# JTAG.net
KiCad netlist of a schematic drawn in Altium Designer
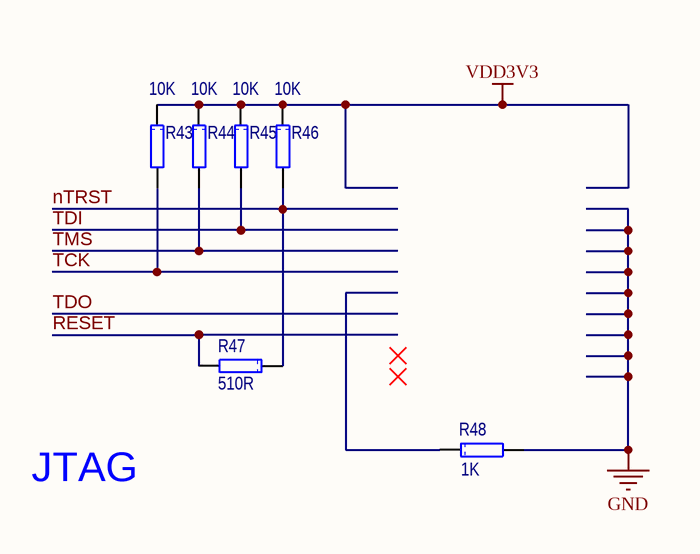
[diagram p0: JTAG.SchDoc]

(export (version "E")
  (design (tool "Eeschema 10.0.6"))
  (components
    (comp (ref "R43")
      (value "10K")
      (footprint "1608[0603]R")
      (description "RES")
      (fields (field (name "MANUFACTURER") "vishay"))
      (libsource (lib "*") (part "RES"))
    )
    (comp (ref "R44")
      (value "10K")
      (footprint "1608[0603]R")
      (description "RES")
      (fields (field (name "MANUFACTURER") "vishay"))
      (libsource (lib "*") (part "RES"))
    )
    (comp (ref "R45")
      (value "10K")
      (footprint "1608[0603]R")
      (description "RES")
      (fields (field (name "MANUFACTURER") "vishay"))
      (libsource (lib "*") (part "RES"))
    )
    (comp (ref "R46")
      (value "10K")
      (footprint "1608[0603]R")
      (description "RES")
      (fields (field (name "MANUFACTURER") "vishay"))
      (libsource (lib "*") (part "RES"))
    )
    (comp (ref "R47")
      (value "510R")
      (footprint "1608[0603]R")
      (description "RES")
      (fields (field (name "MANUFACTURER") "vishay"))
      (libsource (lib "*") (part "RES"))
    )
    (comp (ref "R48")
      (value "1K")
      (description "RES")
      (fields (field (name "MANUFACTURER") "vishay"))
      (libsource (lib "*") (part "RES"))
    )
  )
  (nets
    (net (code "1") (name "/RESET") (class "Default")
      (node (ref "R47") (pin "2") (pinfunction "2_2") (pintype "passive"))
    )
    (net (code "2") (name "/TCK") (class "Default")
      (node (ref "R43") (pin "2") (pinfunction "2_2") (pintype "passive"))
    )
    (net (code "3") (name "/TDI") (class "Default")
      (node (ref "R45") (pin "2") (pinfunction "2_2") (pintype "passive"))
    )
    (net (code "5") (name "/TMS") (class "Default")
      (node (ref "R44") (pin "2") (pinfunction "2_2") (pintype "passive"))
    )
    (net (code "6") (name "/nTRST") (class "Default")
      (node (ref "R46") (pin "2") (pinfunction "2_2") (pintype "passive"))
      (node (ref "R47") (pin "1") (pinfunction "1_1") (pintype "passive"))
    )
    (net (code "7") (name "GND") (class "Default")
      (node (ref "R48") (pin "2") (pinfunction "2_2") (pintype "passive"))
    )
    (net (code "8") (name "VDD3V3") (class "Default")
      (node (ref "R43") (pin "1") (pinfunction "1_1") (pintype "passive"))
      (node (ref "R44") (pin "1") (pinfunction "1_1") (pintype "passive"))
      (node (ref "R45") (pin "1") (pinfunction "1_1") (pintype "passive"))
      (node (ref "R46") (pin "1") (pinfunction "1_1") (pintype "passive"))
    )
    (net (code "9") (name "unconnected-(R48-Pad1)") (class "Default")
      (node (ref "R48") (pin "1") (pinfunction "1_1") (pintype "passive"))
    )
  )
)
